# SPIShortcut.net
KiCad netlist of a schematic drawn in EAGLE
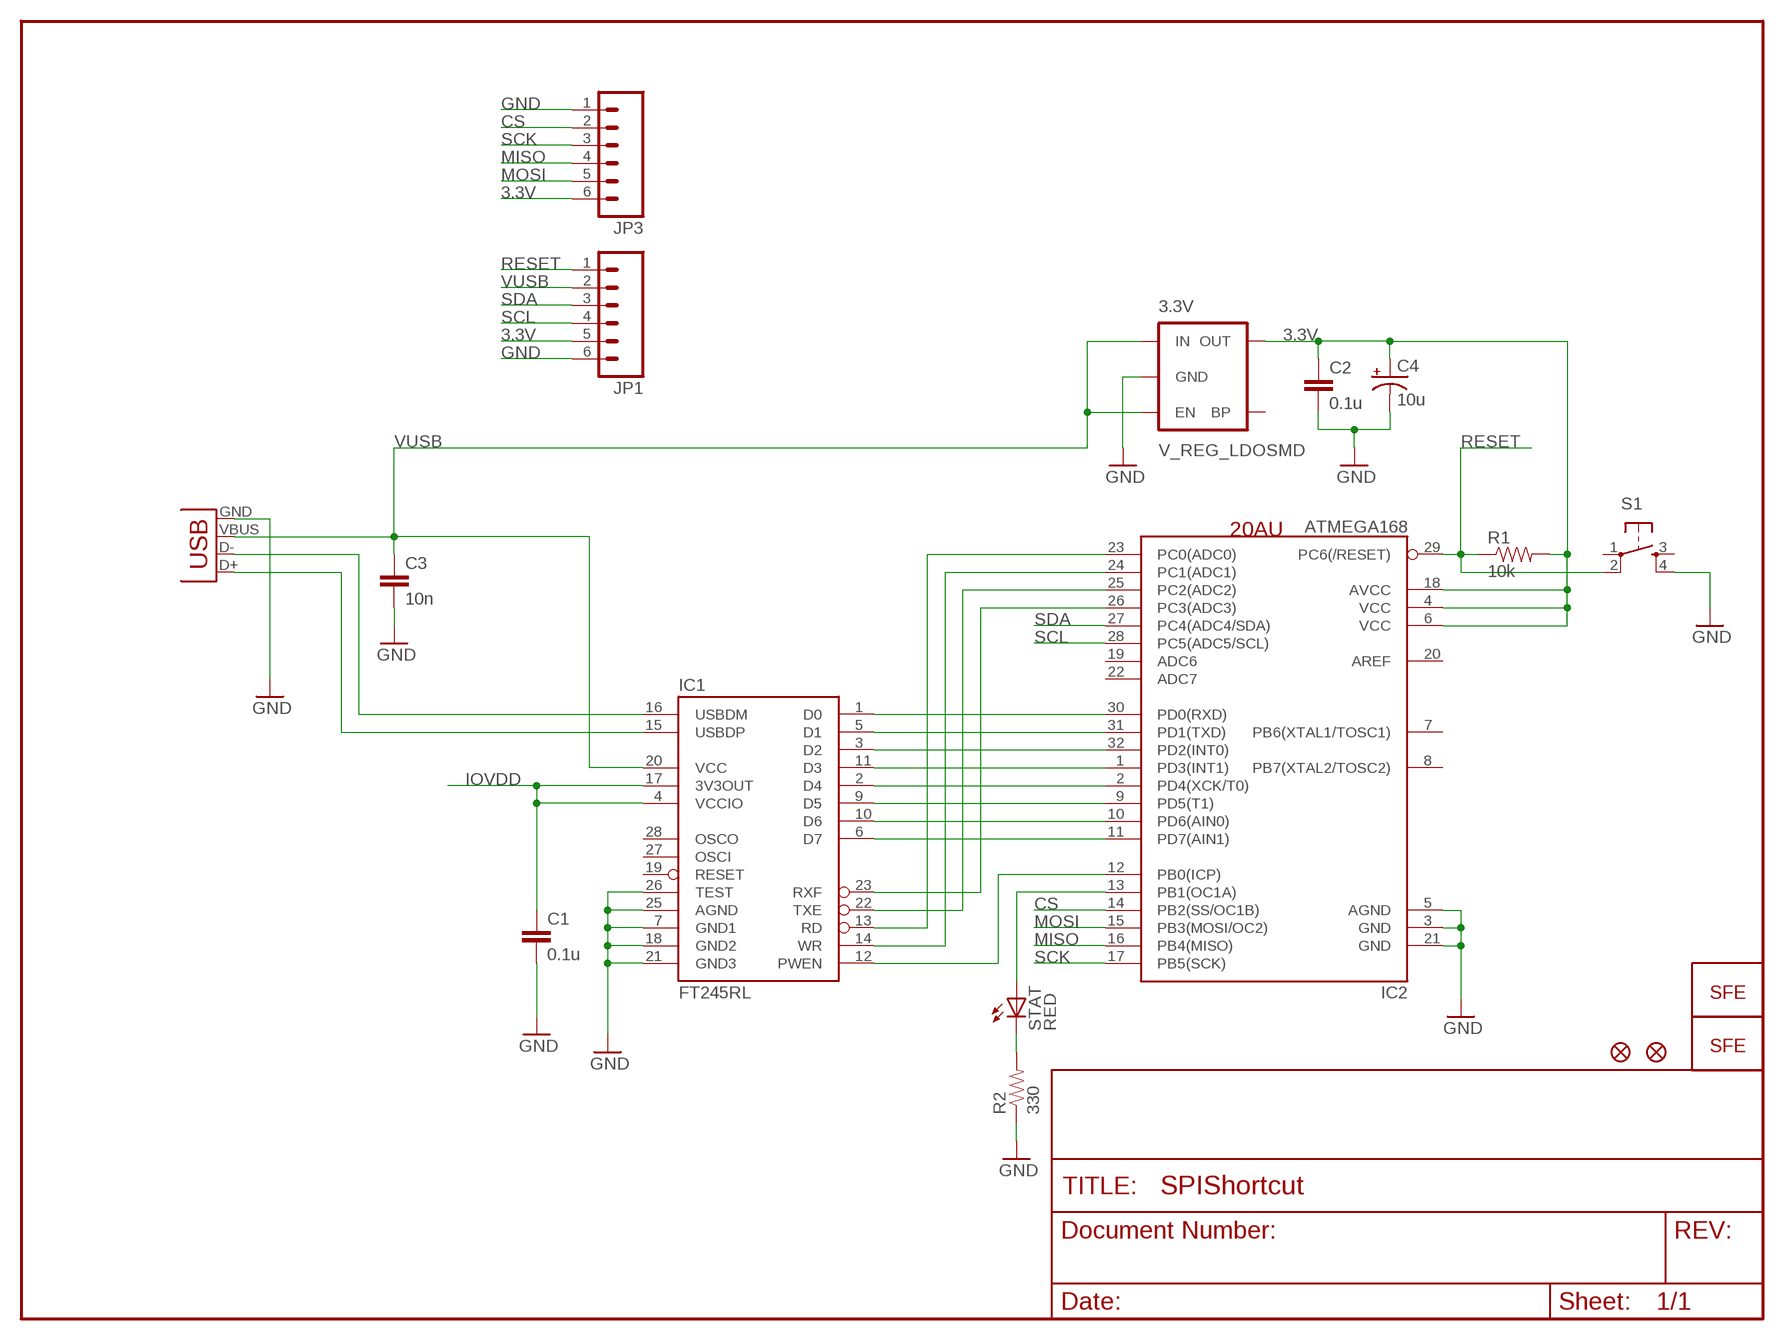
[diagram p0: schematic, sheet 1]

(export (version "E")
  (design (tool "Eeschema 10.0.6"))
  (components
    (comp (ref "3.3V")
      (value "V_REG_LDOSMD")
      (footprint "eagle-import:SOT23-5")
      (libsource (lib "eagle-import") (part "V_REG_LDOSMD"))
    )
    (comp (ref "C1")
      (value "0.1u")
      (footprint "eagle-import:0402-CAP")
      (libsource (lib "eagle-import") (part "CAP0402-CAP"))
    )
    (comp (ref "C2")
      (value "0.1u")
      (footprint "eagle-import:0402-CAP")
      (libsource (lib "eagle-import") (part "CAP0402-CAP"))
    )
    (comp (ref "C3")
      (value "10n")
      (footprint "eagle-import:0402-CAP")
      (libsource (lib "eagle-import") (part "CAP0402-CAP"))
    )
    (comp (ref "C4")
      (value "10u")
      (footprint "eagle-import:EIA3216")
      (libsource (lib "eagle-import") (part "CAP_POL1206"))
    )
    (comp (ref "IC1")
      (value "FT245RL")
      (footprint "eagle-import:SSOP28DB")
      (libsource (lib "eagle-import") (part "FT245RL"))
    )
    (comp (ref "IC2")
      (value "ATMEGA168")
      (footprint "eagle-import:TQFP32-08")
      (libsource (lib "eagle-import") (part "ATMEGA168"))
    )
    (comp (ref "JP1")
      (value "M06SIP")
      (footprint "eagle-import:1X06")
      (libsource (lib "eagle-import") (part "M06SIP"))
    )
    (comp (ref "JP3")
      (value "M06SIP")
      (footprint "eagle-import:1X06")
      (libsource (lib "eagle-import") (part "M06SIP"))
    )
    (comp (ref "R1")
      (value "10k")
      (footprint "eagle-import:0402-RES")
      (libsource (lib "eagle-import") (part "RESISTOR0402-RES"))
    )
    (comp (ref "R2")
      (value "330")
      (footprint "eagle-import:0402-RES")
      (libsource (lib "eagle-import") (part "RESISTOR0402-RES"))
    )
    (comp (ref "S1")
      (value "TAC_SWITCHSMD")
      (footprint "eagle-import:TACTILE_SWITCH_SMD")
      (libsource (lib "eagle-import") (part "TAC_SWITCHSMD"))
    )
    (comp (ref "STAT")
      (value "RED")
      (footprint "eagle-import:LED-0603")
      (libsource (lib "eagle-import") (part "LED0603"))
    )
    (comp (ref "U$3")
      (value "LOGO-SFENEW")
      (footprint "eagle-import:SFE-NEW-WEBLOGO")
      (libsource (lib "eagle-import") (part "LOGO-SFENEW"))
    )
    (comp (ref "U$5")
      (value "FIDUCIAL1X2")
      (footprint "eagle-import:FIDUCIAL-1X2")
      (libsource (lib "eagle-import") (part "FIDUCIAL1X2"))
    )
    (comp (ref "U$6")
      (value "FIDUCIAL1X2")
      (footprint "eagle-import:FIDUCIAL-1X2")
      (libsource (lib "eagle-import") (part "FIDUCIAL1X2"))
    )
    (comp (ref "U$7")
      (value "LOGO-SFESK")
      (footprint "eagle-import:SFE-LOGO-FLAME")
      (libsource (lib "eagle-import") (part "LOGO-SFESK"))
    )
    (comp (ref "X1")
      (value "USBSMD")
      (footprint "eagle-import:USB-MINIB")
      (libsource (lib "eagle-import") (part "USBSMD"))
    )
  )
  (nets
    (net (code "1") (name "/3.3V") (class "Default")
      (node (ref "3.3V") (pin "5") (pinfunction "OUT_5") (pintype "passive"))
      (node (ref "C2") (pin "1") (pinfunction "1_1") (pintype "passive"))
      (node (ref "C4") (pin "A") (pinfunction "+_A") (pintype "passive"))
      (node (ref "IC2") (pin "18") (pinfunction "AVCC_18") (pintype "bidirectional"))
      (node (ref "IC2") (pin "4") (pinfunction "VCC_4") (pintype "bidirectional"))
      (node (ref "IC2") (pin "6") (pinfunction "VCC_6") (pintype "bidirectional"))
      (node (ref "JP1") (pin "5") (pinfunction "5_5") (pintype "passive"))
      (node (ref "JP3") (pin "6") (pinfunction "6_6") (pintype "passive"))
      (node (ref "R1") (pin "2") (pinfunction "2_2") (pintype "passive"))
    )
    (net (code "2") (name "/CS") (class "Default")
      (node (ref "IC2") (pin "14") (pinfunction "PB2(SS/OC1B)_14") (pintype "bidirectional"))
      (node (ref "JP3") (pin "2") (pinfunction "2_2") (pintype "passive"))
    )
    (net (code "3") (name "/IOVDD") (class "Default")
      (node (ref "C1") (pin "1") (pinfunction "1_1") (pintype "passive"))
      (node (ref "IC1") (pin "17") (pinfunction "3V3OUT_17") (pintype "output"))
      (node (ref "IC1") (pin "4") (pinfunction "VCCIO_4") (pintype "power_in"))
    )
    (net (code "4") (name "/MISO") (class "Default")
      (node (ref "IC2") (pin "16") (pinfunction "PB4(MISO)_16") (pintype "bidirectional"))
      (node (ref "JP3") (pin "4") (pinfunction "4_4") (pintype "passive"))
    )
    (net (code "5") (name "/MOSI") (class "Default")
      (node (ref "IC2") (pin "15") (pinfunction "PB3(MOSI/OC2)_15") (pintype "bidirectional"))
      (node (ref "JP3") (pin "5") (pinfunction "5_5") (pintype "passive"))
    )
    (net (code "6") (name "/RESET") (class "Default")
      (node (ref "IC2") (pin "29") (pinfunction "PC6(/RESET)_29") (pintype "bidirectional"))
      (node (ref "JP1") (pin "1") (pinfunction "1_1") (pintype "passive"))
      (node (ref "R1") (pin "1") (pinfunction "1_1") (pintype "passive"))
      (node (ref "S1") (pin "2") (pinfunction "2_2") (pintype "passive"))
    )
    (net (code "7") (name "/SCK") (class "Default")
      (node (ref "IC2") (pin "17") (pinfunction "PB5(SCK)_17") (pintype "bidirectional"))
      (node (ref "JP3") (pin "3") (pinfunction "3_3") (pintype "passive"))
    )
    (net (code "8") (name "/SCL") (class "Default")
      (node (ref "IC2") (pin "28") (pinfunction "PC5(ADC5/SCL)_28") (pintype "bidirectional"))
      (node (ref "JP1") (pin "4") (pinfunction "4_4") (pintype "passive"))
    )
    (net (code "9") (name "/SDA") (class "Default")
      (node (ref "IC2") (pin "27") (pinfunction "PC4(ADC4/SDA)_27") (pintype "bidirectional"))
      (node (ref "JP1") (pin "3") (pinfunction "3_3") (pintype "passive"))
    )
    (net (code "10") (name "/VUSB") (class "Default")
      (node (ref "3.3V") (pin "1") (pinfunction "IN_1") (pintype "input"))
      (node (ref "3.3V") (pin "3") (pinfunction "EN_3") (pintype "input"))
      (node (ref "C3") (pin "1") (pinfunction "1_1") (pintype "passive"))
      (node (ref "IC1") (pin "20") (pinfunction "VCC_20") (pintype "power_in"))
      (node (ref "JP1") (pin "2") (pinfunction "2_2") (pintype "passive"))
      (node (ref "X1") (pin "VBUS") (pinfunction "VBUS_VBUS") (pintype "bidirectional"))
    )
    (net (code "11") (name "GND") (class "Default")
      (node (ref "3.3V") (pin "2") (pinfunction "GND_2") (pintype "input"))
      (node (ref "C1") (pin "2") (pinfunction "2_2") (pintype "passive"))
      (node (ref "C2") (pin "2") (pinfunction "2_2") (pintype "passive"))
      (node (ref "C3") (pin "2") (pinfunction "2_2") (pintype "passive"))
      (node (ref "C4") (pin "C") (pinfunction "-_C") (pintype "passive"))
      (node (ref "IC1") (pin "18") (pinfunction "GND2_18") (pintype "power_in"))
      (node (ref "IC1") (pin "21") (pinfunction "GND3_21") (pintype "power_in"))
      (node (ref "IC1") (pin "25") (pinfunction "AGND_25") (pintype "power_in"))
      (node (ref "IC1") (pin "26") (pinfunction "TEST_26") (pintype "input"))
      (node (ref "IC1") (pin "7") (pinfunction "GND1_7") (pintype "power_in"))
      (node (ref "IC2") (pin "21") (pinfunction "GND_21") (pintype "bidirectional"))
      (node (ref "IC2") (pin "3") (pinfunction "GND_3") (pintype "bidirectional"))
      (node (ref "IC2") (pin "5") (pinfunction "AGND_5") (pintype "bidirectional"))
      (node (ref "JP1") (pin "6") (pinfunction "6_6") (pintype "passive"))
      (node (ref "JP3") (pin "1") (pinfunction "1_1") (pintype "passive"))
      (node (ref "R2") (pin "1") (pinfunction "1_1") (pintype "passive"))
      (node (ref "S1") (pin "4") (pinfunction "4_4") (pintype "passive"))
      (node (ref "X1") (pin "GND") (pinfunction "GND_GND") (pintype "bidirectional"))
    )
    (net (code "12") (name "Net-(IC1-D0)") (class "Default")
      (node (ref "IC1") (pin "1") (pinfunction "D0_1") (pintype "output"))
      (node (ref "IC2") (pin "30") (pinfunction "PD0(RXD)_30") (pintype "bidirectional"))
    )
    (net (code "13") (name "Net-(IC1-D1)") (class "Default")
      (node (ref "IC1") (pin "5") (pinfunction "D1_5") (pintype "input"))
      (node (ref "IC2") (pin "31") (pinfunction "PD1(TXD)_31") (pintype "bidirectional"))
    )
    (net (code "14") (name "Net-(IC1-D2)") (class "Default")
      (node (ref "IC1") (pin "3") (pinfunction "D2_3") (pintype "output"))
      (node (ref "IC2") (pin "32") (pinfunction "PD2(INT0)_32") (pintype "bidirectional"))
    )
    (net (code "15") (name "Net-(IC1-D3)") (class "Default")
      (node (ref "IC1") (pin "11") (pinfunction "D3_11") (pintype "input"))
      (node (ref "IC2") (pin "1") (pinfunction "PD3(INT1)_1") (pintype "bidirectional"))
    )
    (net (code "16") (name "Net-(IC1-D4)") (class "Default")
      (node (ref "IC1") (pin "2") (pinfunction "D4_2") (pintype "output"))
      (node (ref "IC2") (pin "2") (pinfunction "PD4(XCK/T0)_2") (pintype "bidirectional"))
    )
    (net (code "17") (name "Net-(IC1-D5)") (class "Default")
      (node (ref "IC1") (pin "9") (pinfunction "D5_9") (pintype "input"))
      (node (ref "IC2") (pin "9") (pinfunction "PD5(T1)_9") (pintype "bidirectional"))
    )
    (net (code "18") (name "Net-(IC1-D6)") (class "Default")
      (node (ref "IC1") (pin "10") (pinfunction "D6_10") (pintype "input"))
      (node (ref "IC2") (pin "10") (pinfunction "PD6(AIN0)_10") (pintype "bidirectional"))
    )
    (net (code "19") (name "Net-(IC1-D7)") (class "Default")
      (node (ref "IC1") (pin "6") (pinfunction "D7_6") (pintype "input"))
      (node (ref "IC2") (pin "11") (pinfunction "PD7(AIN1)_11") (pintype "bidirectional"))
    )
    (net (code "20") (name "Net-(IC1-PWEN)") (class "Default")
      (node (ref "IC1") (pin "12") (pinfunction "PWEN_12") (pintype "bidirectional"))
      (node (ref "IC2") (pin "12") (pinfunction "PB0(ICP)_12") (pintype "bidirectional"))
    )
    (net (code "21") (name "Net-(IC1-RD)") (class "Default")
      (node (ref "IC1") (pin "13") (pinfunction "RD_13") (pintype "bidirectional"))
      (node (ref "IC2") (pin "23") (pinfunction "PC0(ADC0)_23") (pintype "bidirectional"))
    )
    (net (code "22") (name "Net-(IC1-RXF)") (class "Default")
      (node (ref "IC1") (pin "23") (pinfunction "RXF_23") (pintype "bidirectional"))
      (node (ref "IC2") (pin "26") (pinfunction "PC3(ADC3)_26") (pintype "bidirectional"))
    )
    (net (code "23") (name "Net-(IC1-TXE)") (class "Default")
      (node (ref "IC1") (pin "22") (pinfunction "TXE_22") (pintype "bidirectional"))
      (node (ref "IC2") (pin "25") (pinfunction "PC2(ADC2)_25") (pintype "bidirectional"))
    )
    (net (code "24") (name "Net-(IC1-USBDM)") (class "Default")
      (node (ref "IC1") (pin "16") (pinfunction "USBDM_16") (pintype "bidirectional"))
      (node (ref "X1") (pin "D-") (pinfunction "D-_D-") (pintype "bidirectional"))
    )
    (net (code "25") (name "Net-(IC1-USBDP)") (class "Default")
      (node (ref "IC1") (pin "15") (pinfunction "USBDP_15") (pintype "bidirectional"))
      (node (ref "X1") (pin "D+") (pinfunction "D+_D+") (pintype "bidirectional"))
    )
    (net (code "26") (name "Net-(IC1-WR)") (class "Default")
      (node (ref "IC1") (pin "14") (pinfunction "WR_14") (pintype "bidirectional"))
      (node (ref "IC2") (pin "24") (pinfunction "PC1(ADC1)_24") (pintype "bidirectional"))
    )
    (net (code "27") (name "Net-(IC2-PB1(OC1A))") (class "Default")
      (node (ref "IC2") (pin "13") (pinfunction "PB1(OC1A)_13") (pintype "bidirectional"))
      (node (ref "STAT") (pin "A") (pinfunction "A_A") (pintype "passive"))
    )
    (net (code "28") (name "Net-(R2-Pad2)") (class "Default")
      (node (ref "R2") (pin "2") (pinfunction "2_2") (pintype "passive"))
      (node (ref "STAT") (pin "C") (pinfunction "C_C") (pintype "passive"))
    )
    (net (code "29") (name "unconnected-(3.3V-BP-Pad4)") (class "Default")
      (node (ref "3.3V") (pin "4") (pinfunction "BP_4") (pintype "input"))
    )
    (net (code "30") (name "unconnected-(IC1-OSCI-Pad27)") (class "Default")
      (node (ref "IC1") (pin "27") (pinfunction "OSCI_27") (pintype "input"))
    )
    (net (code "31") (name "unconnected-(IC1-OSCO-Pad28)") (class "Default")
      (node (ref "IC1") (pin "28") (pinfunction "OSCO_28") (pintype "output"))
    )
    (net (code "32") (name "unconnected-(IC1-RESET-Pad19)") (class "Default")
      (node (ref "IC1") (pin "19") (pinfunction "RESET_19") (pintype "input"))
    )
    (net (code "33") (name "unconnected-(IC2-ADC6-Pad19)") (class "Default")
      (node (ref "IC2") (pin "19") (pinfunction "ADC6_19") (pintype "bidirectional"))
    )
    (net (code "34") (name "unconnected-(IC2-ADC7-Pad22)") (class "Default")
      (node (ref "IC2") (pin "22") (pinfunction "ADC7_22") (pintype "bidirectional"))
    )
    (net (code "35") (name "unconnected-(IC2-AREF-Pad20)") (class "Default")
      (node (ref "IC2") (pin "20") (pinfunction "AREF_20") (pintype "bidirectional"))
    )
    (net (code "36") (name "unconnected-(IC2-PB6(XTAL1{slash}TOSC1)-Pad7)") (class "Default")
      (node (ref "IC2") (pin "7") (pinfunction "PB6(XTAL1/TOSC1)_7") (pintype "bidirectional"))
    )
    (net (code "37") (name "unconnected-(IC2-PB7(XTAL2{slash}TOSC2)-Pad8)") (class "Default")
      (node (ref "IC2") (pin "8") (pinfunction "PB7(XTAL2/TOSC2)_8") (pintype "bidirectional"))
    )
    (net (code "38") (name "unconnected-(S1-Pad1)") (class "Default")
      (node (ref "S1") (pin "1") (pinfunction "1_1") (pintype "passive"))
    )
    (net (code "39") (name "unconnected-(S1-Pad3)") (class "Default")
      (node (ref "S1") (pin "3") (pinfunction "3_3") (pintype "passive"))
    )
  )
)
